# Channel.net
KiCad netlist of a schematic drawn in Altium Designer
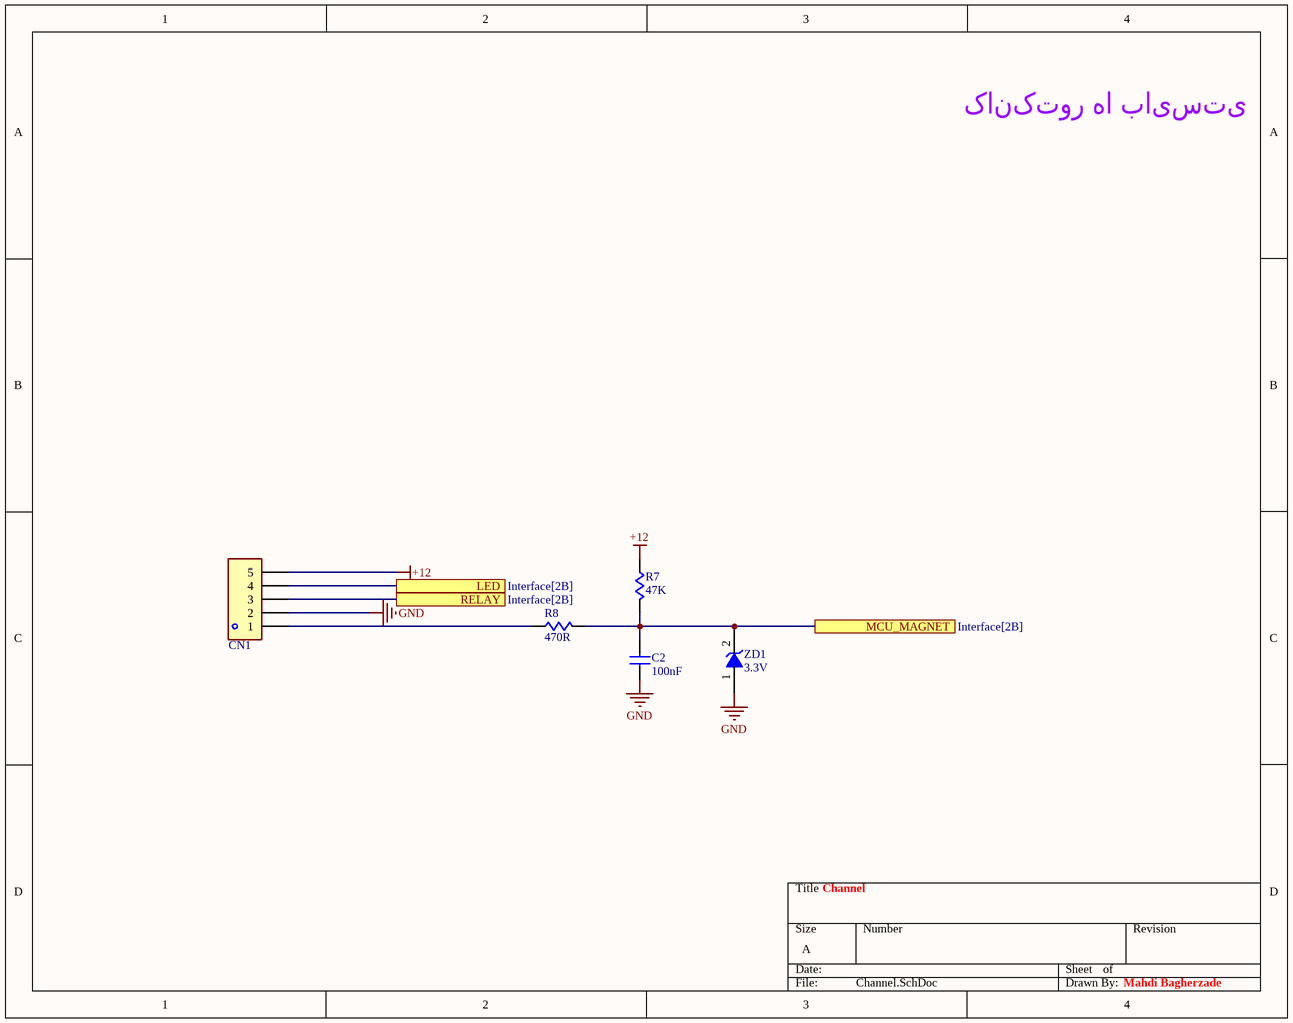
[diagram p0: Channel.SchDoc]

(export (version "E")
  (design (tool "Eeschema 10.0.6"))
  (components
    (comp (ref "C2")
      (value "100nF")
      (footprint "C-0805")
      (description "CAPACITOR")
      (fields
        (field (name "VOLTAGE") "50V")
        (field (name "TOLERANCE") "X7R")
        (field (name "PUBLISHER") "Mahdi Bagherzadeh")
      )
      (libsource (lib "Mahdi-Bagherzadeh") (part "CAP-CER"))
    )
    (comp (ref "CN1")
      (value "Connector XH/VH/TE-Straight/Right-THD/SMD-?mm")
      (footprint "XH-5")
      (description "CONNECTOR")
      (fields (field (name "PUBLISHER") "Mahdi Bagherzadeh"))
      (libsource (lib "Mahdi-Bagherzadeh") (part "CN-5pin"))
    )
    (comp (ref "R7")
      (value "47K")
      (footprint "R-0805")
      (description "RESISTOR")
      (fields
        (field (name "TOLERANCE") "5%")
        (field (name "POWER") "1/8W")
        (field (name "PUBLISHER") "Mahdi Bagherzadeh")
      )
      (libsource (lib "Mahdi-Bagherzadeh") (part "RES"))
    )
    (comp (ref "R8")
      (value "470R")
      (footprint "R-0805")
      (description "RESISTOR")
      (fields
        (field (name "TOLERANCE") "5%")
        (field (name "POWER") "1/8W")
        (field (name "PUBLISHER") "Mahdi Bagherzadeh")
      )
      (libsource (lib "Mahdi-Bagherzadeh") (part "RES"))
    )
    (comp (ref "ZD1")
      (value "Zener -3.3V-SMD")
      (footprint "SOD80")
      (description "DIODE")
      (fields
        (field (name "POWER") "Minimelf")
        (field (name "VOLTAGE") "3.3V")
        (field (name "PUBLISHER") "Mahdi Bagherzadeh")
      )
      (libsource (lib "Mahdi-Bagherzadeh") (part "DIODE-ZENER"))
    )
  )
  (nets
    (net (code "1") (name "+12") (class "Default")
      (node (ref "CN1") (pin "5") (pinfunction "5_5") (pintype "passive"))
      (node (ref "R7") (pin "1") (pinfunction "1_1") (pintype "passive"))
    )
    (net (code "2") (name "/LED") (class "Default")
      (node (ref "CN1") (pin "4") (pinfunction "4_4") (pintype "passive"))
    )
    (net (code "3") (name "/MCU_MAGNET") (class "Default")
      (node (ref "C2") (pin "1") (pinfunction "1_1") (pintype "passive"))
      (node (ref "R7") (pin "2") (pinfunction "2_2") (pintype "passive"))
      (node (ref "R8") (pin "2") (pinfunction "2_2") (pintype "passive"))
      (node (ref "ZD1") (pin "2") (pinfunction "C_2") (pintype "passive"))
    )
    (net (code "4") (name "/RELAY") (class "Default")
      (node (ref "CN1") (pin "3") (pinfunction "3_3") (pintype "passive"))
    )
    (net (code "5") (name "GND") (class "Default")
      (node (ref "C2") (pin "2") (pinfunction "2_2") (pintype "passive"))
      (node (ref "CN1") (pin "2") (pinfunction "2_2") (pintype "passive"))
      (node (ref "ZD1") (pin "1") (pinfunction "A_1") (pintype "passive"))
    )
    (net (code "6") (name "Net-(CN1-Pad1)") (class "Default")
      (node (ref "CN1") (pin "1") (pinfunction "1_1") (pintype "passive"))
      (node (ref "R8") (pin "1") (pinfunction "1_1") (pintype "passive"))
    )
  )
)
